# DIP_SWITCH.net
KiCad netlist of a schematic drawn in Altium Designer
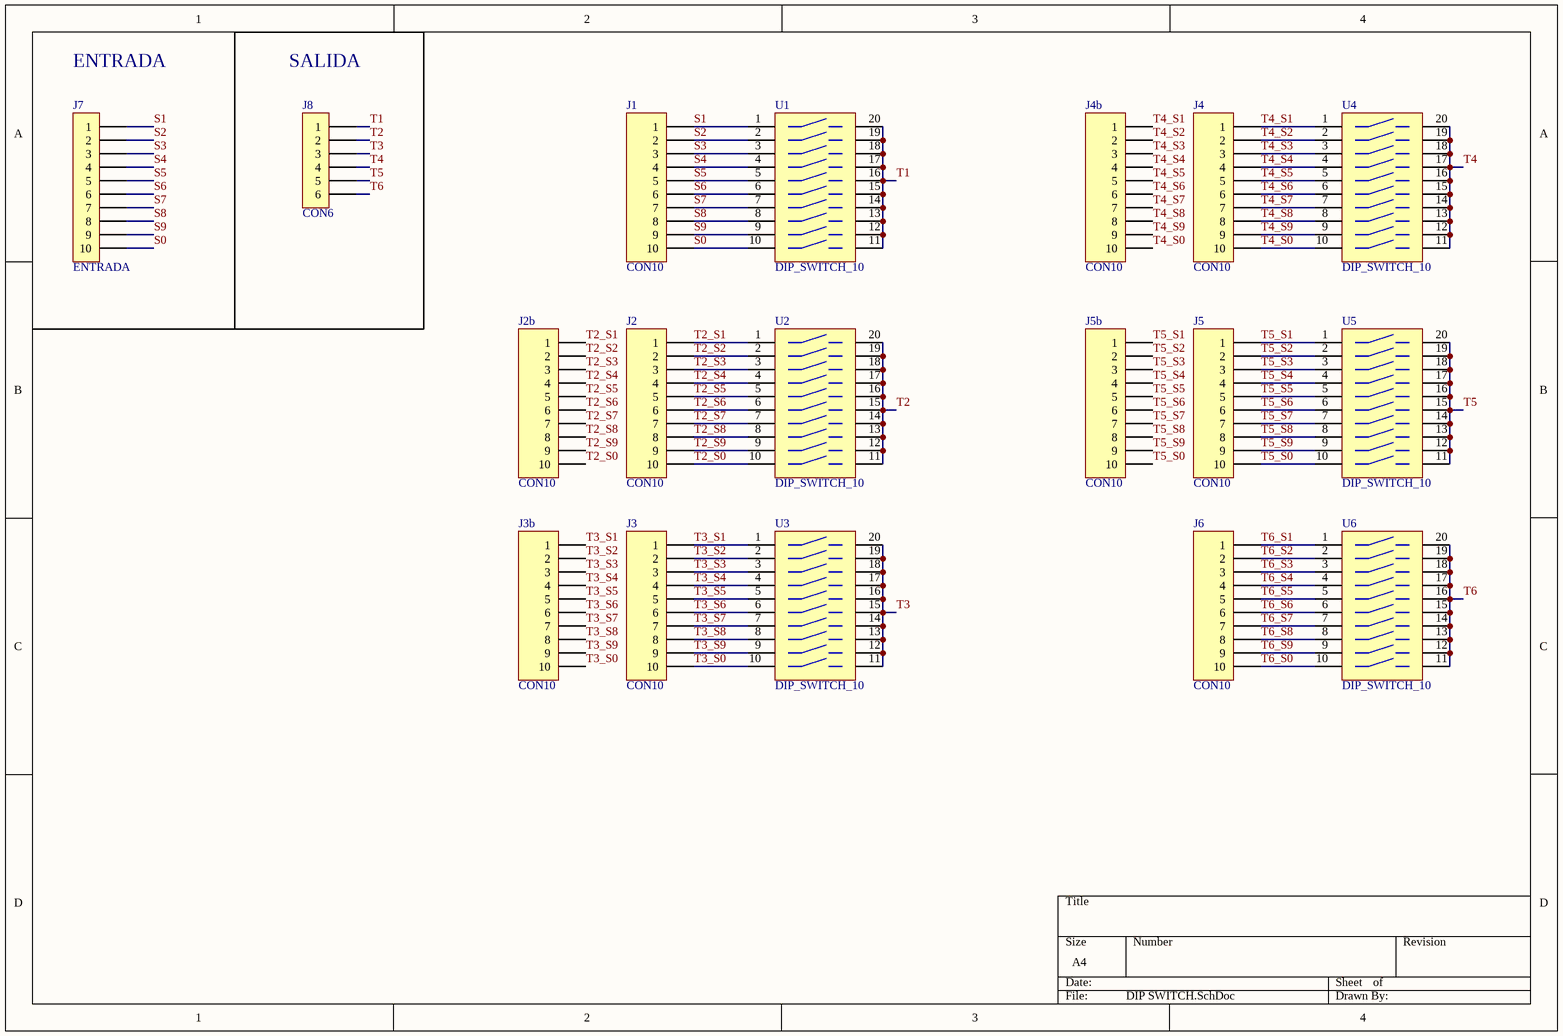
[diagram p0: DIP SWITCH.SchDoc]

(export (version "E")
  (design (tool "Eeschema 10.0.6"))
  (components
    (comp (ref "J1") (value "CON10") (footprint "SIP10") (libsource (lib "Libreria4") (part "CON10")))
    (comp (ref "J2") (value "CON10") (footprint "SIP10") (libsource (lib "Libreria4") (part "CON10")))
    (comp (ref "J2b") (value "CON10") (footprint "SIP10") (libsource (lib "Libreria4") (part "CON10")))
    (comp (ref "J3") (value "CON10") (footprint "SIP10") (libsource (lib "Libreria4") (part "CON10")))
    (comp (ref "J3b") (value "CON10") (footprint "SIP10") (libsource (lib "Libreria4") (part "CON10")))
    (comp (ref "J4") (value "CON10") (footprint "SIP10") (libsource (lib "Libreria4") (part "CON10")))
    (comp (ref "J4b") (value "CON10") (footprint "SIP10") (libsource (lib "Libreria4") (part "CON10")))
    (comp (ref "J5") (value "CON10") (footprint "SIP10") (libsource (lib "Libreria4") (part "CON10")))
    (comp (ref "J5b") (value "CON10") (footprint "SIP10") (libsource (lib "Libreria4") (part "CON10")))
    (comp (ref "J6") (value "CON10") (footprint "SIP10") (libsource (lib "Libreria4") (part "CON10")))
    (comp (ref "J7")
      (value "ENTRADA")
      (footprint "BORNERA10")
      (libsource (lib "Libreria4") (part "BORNERA10"))
    )
    (comp (ref "J8") (value "CON6") (footprint "SIP6") (libsource (lib "Libreria4") (part "CON6")))
    (comp (ref "U1")
      (value "DIP_SWITCH_10")
      (footprint "DIP20")
      (description "Dip_Switch 10 Posiciones")
      (libsource (lib "Libreria Buena Onda V5") (part "DIPSWITCH10"))
    )
    (comp (ref "U2")
      (value "DIP_SWITCH_10")
      (footprint "DIP20")
      (description "Dip_Switch 10 Posiciones")
      (libsource (lib "Libreria Buena Onda V5") (part "DIPSWITCH10"))
    )
    (comp (ref "U3")
      (value "DIP_SWITCH_10")
      (footprint "DIP20")
      (description "Dip_Switch 10 Posiciones")
      (libsource (lib "Libreria Buena Onda V5") (part "DIPSWITCH10"))
    )
    (comp (ref "U4")
      (value "DIP_SWITCH_10")
      (footprint "DIP20")
      (description "Dip_Switch 10 Posiciones")
      (libsource (lib "Libreria Buena Onda V5") (part "DIPSWITCH10"))
    )
    (comp (ref "U5")
      (value "DIP_SWITCH_10")
      (footprint "DIP20")
      (description "Dip_Switch 10 Posiciones")
      (libsource (lib "Libreria Buena Onda V5") (part "DIPSWITCH10"))
    )
    (comp (ref "U6")
      (value "DIP_SWITCH_10")
      (footprint "DIP20")
      (description "Dip_Switch 10 Posiciones")
      (libsource (lib "Libreria Buena Onda V5") (part "DIPSWITCH10"))
    )
  )
  (nets
    (net (code "1") (name "/S0") (class "Default")
      (node (ref "J1") (pin "10") (pinfunction "10_10") (pintype "passive"))
      (node (ref "J7") (pin "10") (pinfunction "10_10") (pintype "passive"))
      (node (ref "U1") (pin "10") (pinfunction "10_10") (pintype "passive"))
    )
    (net (code "2") (name "/S1") (class "Default")
      (node (ref "J1") (pin "1") (pinfunction "1_1") (pintype "passive"))
      (node (ref "J7") (pin "1") (pinfunction "1_1") (pintype "passive"))
      (node (ref "U1") (pin "1") (pinfunction "1_1") (pintype "passive"))
    )
    (net (code "3") (name "/S2") (class "Default")
      (node (ref "J1") (pin "2") (pinfunction "2_2") (pintype "passive"))
      (node (ref "J7") (pin "2") (pinfunction "2_2") (pintype "passive"))
      (node (ref "U1") (pin "2") (pinfunction "2_2") (pintype "passive"))
    )
    (net (code "4") (name "/S3") (class "Default")
      (node (ref "J1") (pin "3") (pinfunction "3_3") (pintype "passive"))
      (node (ref "J7") (pin "3") (pinfunction "3_3") (pintype "passive"))
      (node (ref "U1") (pin "3") (pinfunction "3_3") (pintype "passive"))
    )
    (net (code "5") (name "/S4") (class "Default")
      (node (ref "J1") (pin "4") (pinfunction "4_4") (pintype "passive"))
      (node (ref "J7") (pin "4") (pinfunction "4_4") (pintype "passive"))
      (node (ref "U1") (pin "4") (pinfunction "4_4") (pintype "passive"))
    )
    (net (code "6") (name "/S5") (class "Default")
      (node (ref "J1") (pin "5") (pinfunction "5_5") (pintype "passive"))
      (node (ref "J7") (pin "5") (pinfunction "5_5") (pintype "passive"))
      (node (ref "U1") (pin "5") (pinfunction "5_5") (pintype "passive"))
    )
    (net (code "7") (name "/S6") (class "Default")
      (node (ref "J1") (pin "6") (pinfunction "6_6") (pintype "passive"))
      (node (ref "J7") (pin "6") (pinfunction "6_6") (pintype "passive"))
      (node (ref "U1") (pin "6") (pinfunction "6_6") (pintype "passive"))
    )
    (net (code "8") (name "/S7") (class "Default")
      (node (ref "J1") (pin "7") (pinfunction "7_7") (pintype "passive"))
      (node (ref "J7") (pin "7") (pinfunction "7_7") (pintype "passive"))
      (node (ref "U1") (pin "7") (pinfunction "7_7") (pintype "passive"))
    )
    (net (code "9") (name "/S8") (class "Default")
      (node (ref "J1") (pin "8") (pinfunction "8_8") (pintype "passive"))
      (node (ref "J7") (pin "8") (pinfunction "8_8") (pintype "passive"))
      (node (ref "U1") (pin "8") (pinfunction "8_8") (pintype "passive"))
    )
    (net (code "10") (name "/S9") (class "Default")
      (node (ref "J1") (pin "9") (pinfunction "9_9") (pintype "passive"))
      (node (ref "J7") (pin "9") (pinfunction "9_9") (pintype "passive"))
      (node (ref "U1") (pin "9") (pinfunction "9_9") (pintype "passive"))
    )
    (net (code "11") (name "/T1") (class "Default")
      (node (ref "J8") (pin "1") (pinfunction "1_1") (pintype "passive"))
      (node (ref "U1") (pin "11") (pinfunction "11_11") (pintype "passive"))
      (node (ref "U1") (pin "12") (pinfunction "12_12") (pintype "passive"))
      (node (ref "U1") (pin "13") (pinfunction "13_13") (pintype "passive"))
      (node (ref "U1") (pin "14") (pinfunction "14_14") (pintype "passive"))
      (node (ref "U1") (pin "15") (pinfunction "15_15") (pintype "passive"))
      (node (ref "U1") (pin "16") (pinfunction "16_16") (pintype "passive"))
      (node (ref "U1") (pin "17") (pinfunction "17_17") (pintype "passive"))
      (node (ref "U1") (pin "18") (pinfunction "18_18") (pintype "passive"))
      (node (ref "U1") (pin "19") (pinfunction "19_19") (pintype "passive"))
      (node (ref "U1") (pin "20") (pinfunction "20_20") (pintype "passive"))
    )
    (net (code "12") (name "/T2") (class "Default")
      (node (ref "J8") (pin "2") (pinfunction "2_2") (pintype "passive"))
      (node (ref "U2") (pin "11") (pinfunction "11_11") (pintype "passive"))
      (node (ref "U2") (pin "12") (pinfunction "12_12") (pintype "passive"))
      (node (ref "U2") (pin "13") (pinfunction "13_13") (pintype "passive"))
      (node (ref "U2") (pin "14") (pinfunction "14_14") (pintype "passive"))
      (node (ref "U2") (pin "15") (pinfunction "15_15") (pintype "passive"))
      (node (ref "U2") (pin "16") (pinfunction "16_16") (pintype "passive"))
      (node (ref "U2") (pin "17") (pinfunction "17_17") (pintype "passive"))
      (node (ref "U2") (pin "18") (pinfunction "18_18") (pintype "passive"))
      (node (ref "U2") (pin "19") (pinfunction "19_19") (pintype "passive"))
      (node (ref "U2") (pin "20") (pinfunction "20_20") (pintype "passive"))
    )
    (net (code "13") (name "/T2_S0") (class "Default")
      (node (ref "J2") (pin "10") (pinfunction "10_10") (pintype "passive"))
      (node (ref "J2b") (pin "10") (pinfunction "10_10") (pintype "passive"))
      (node (ref "U2") (pin "10") (pinfunction "10_10") (pintype "passive"))
    )
    (net (code "14") (name "/T2_S1") (class "Default")
      (node (ref "J2") (pin "1") (pinfunction "1_1") (pintype "passive"))
      (node (ref "J2b") (pin "1") (pinfunction "1_1") (pintype "passive"))
      (node (ref "U2") (pin "1") (pinfunction "1_1") (pintype "passive"))
    )
    (net (code "15") (name "/T2_S2") (class "Default")
      (node (ref "J2") (pin "2") (pinfunction "2_2") (pintype "passive"))
      (node (ref "J2b") (pin "2") (pinfunction "2_2") (pintype "passive"))
      (node (ref "U2") (pin "2") (pinfunction "2_2") (pintype "passive"))
    )
    (net (code "16") (name "/T2_S3") (class "Default")
      (node (ref "J2") (pin "3") (pinfunction "3_3") (pintype "passive"))
      (node (ref "J2b") (pin "3") (pinfunction "3_3") (pintype "passive"))
      (node (ref "U2") (pin "3") (pinfunction "3_3") (pintype "passive"))
    )
    (net (code "17") (name "/T2_S4") (class "Default")
      (node (ref "J2") (pin "4") (pinfunction "4_4") (pintype "passive"))
      (node (ref "J2b") (pin "4") (pinfunction "4_4") (pintype "passive"))
      (node (ref "U2") (pin "4") (pinfunction "4_4") (pintype "passive"))
    )
    (net (code "18") (name "/T2_S5") (class "Default")
      (node (ref "J2") (pin "5") (pinfunction "5_5") (pintype "passive"))
      (node (ref "J2b") (pin "5") (pinfunction "5_5") (pintype "passive"))
      (node (ref "U2") (pin "5") (pinfunction "5_5") (pintype "passive"))
    )
    (net (code "19") (name "/T2_S6") (class "Default")
      (node (ref "J2") (pin "6") (pinfunction "6_6") (pintype "passive"))
      (node (ref "J2b") (pin "6") (pinfunction "6_6") (pintype "passive"))
      (node (ref "U2") (pin "6") (pinfunction "6_6") (pintype "passive"))
    )
    (net (code "20") (name "/T2_S7") (class "Default")
      (node (ref "J2") (pin "7") (pinfunction "7_7") (pintype "passive"))
      (node (ref "J2b") (pin "7") (pinfunction "7_7") (pintype "passive"))
      (node (ref "U2") (pin "7") (pinfunction "7_7") (pintype "passive"))
    )
    (net (code "21") (name "/T2_S8") (class "Default")
      (node (ref "J2") (pin "8") (pinfunction "8_8") (pintype "passive"))
      (node (ref "J2b") (pin "8") (pinfunction "8_8") (pintype "passive"))
      (node (ref "U2") (pin "8") (pinfunction "8_8") (pintype "passive"))
    )
    (net (code "22") (name "/T2_S9") (class "Default")
      (node (ref "J2") (pin "9") (pinfunction "9_9") (pintype "passive"))
      (node (ref "J2b") (pin "9") (pinfunction "9_9") (pintype "passive"))
      (node (ref "U2") (pin "9") (pinfunction "9_9") (pintype "passive"))
    )
    (net (code "23") (name "/T3") (class "Default")
      (node (ref "J8") (pin "3") (pinfunction "3_3") (pintype "passive"))
      (node (ref "U3") (pin "11") (pinfunction "11_11") (pintype "passive"))
      (node (ref "U3") (pin "12") (pinfunction "12_12") (pintype "passive"))
      (node (ref "U3") (pin "13") (pinfunction "13_13") (pintype "passive"))
      (node (ref "U3") (pin "14") (pinfunction "14_14") (pintype "passive"))
      (node (ref "U3") (pin "15") (pinfunction "15_15") (pintype "passive"))
      (node (ref "U3") (pin "16") (pinfunction "16_16") (pintype "passive"))
      (node (ref "U3") (pin "17") (pinfunction "17_17") (pintype "passive"))
      (node (ref "U3") (pin "18") (pinfunction "18_18") (pintype "passive"))
      (node (ref "U3") (pin "19") (pinfunction "19_19") (pintype "passive"))
      (node (ref "U3") (pin "20") (pinfunction "20_20") (pintype "passive"))
    )
    (net (code "24") (name "/T3_S0") (class "Default")
      (node (ref "J3") (pin "10") (pinfunction "10_10") (pintype "passive"))
      (node (ref "J3b") (pin "10") (pinfunction "10_10") (pintype "passive"))
      (node (ref "U3") (pin "10") (pinfunction "10_10") (pintype "passive"))
    )
    (net (code "25") (name "/T3_S1") (class "Default")
      (node (ref "J3") (pin "1") (pinfunction "1_1") (pintype "passive"))
      (node (ref "J3b") (pin "1") (pinfunction "1_1") (pintype "passive"))
      (node (ref "U3") (pin "1") (pinfunction "1_1") (pintype "passive"))
    )
    (net (code "26") (name "/T3_S2") (class "Default")
      (node (ref "J3") (pin "2") (pinfunction "2_2") (pintype "passive"))
      (node (ref "J3b") (pin "2") (pinfunction "2_2") (pintype "passive"))
      (node (ref "U3") (pin "2") (pinfunction "2_2") (pintype "passive"))
    )
    (net (code "27") (name "/T3_S3") (class "Default")
      (node (ref "J3") (pin "3") (pinfunction "3_3") (pintype "passive"))
      (node (ref "J3b") (pin "3") (pinfunction "3_3") (pintype "passive"))
      (node (ref "U3") (pin "3") (pinfunction "3_3") (pintype "passive"))
    )
    (net (code "28") (name "/T3_S4") (class "Default")
      (node (ref "J3") (pin "4") (pinfunction "4_4") (pintype "passive"))
      (node (ref "J3b") (pin "4") (pinfunction "4_4") (pintype "passive"))
      (node (ref "U3") (pin "4") (pinfunction "4_4") (pintype "passive"))
    )
    (net (code "29") (name "/T3_S5") (class "Default")
      (node (ref "J3") (pin "5") (pinfunction "5_5") (pintype "passive"))
      (node (ref "J3b") (pin "5") (pinfunction "5_5") (pintype "passive"))
      (node (ref "U3") (pin "5") (pinfunction "5_5") (pintype "passive"))
    )
    (net (code "30") (name "/T3_S6") (class "Default")
      (node (ref "J3") (pin "6") (pinfunction "6_6") (pintype "passive"))
      (node (ref "J3b") (pin "6") (pinfunction "6_6") (pintype "passive"))
      (node (ref "U3") (pin "6") (pinfunction "6_6") (pintype "passive"))
    )
    (net (code "31") (name "/T3_S7") (class "Default")
      (node (ref "J3") (pin "7") (pinfunction "7_7") (pintype "passive"))
      (node (ref "J3b") (pin "7") (pinfunction "7_7") (pintype "passive"))
      (node (ref "U3") (pin "7") (pinfunction "7_7") (pintype "passive"))
    )
    (net (code "32") (name "/T3_S8") (class "Default")
      (node (ref "J3") (pin "8") (pinfunction "8_8") (pintype "passive"))
      (node (ref "J3b") (pin "8") (pinfunction "8_8") (pintype "passive"))
      (node (ref "U3") (pin "8") (pinfunction "8_8") (pintype "passive"))
    )
    (net (code "33") (name "/T3_S9") (class "Default")
      (node (ref "J3") (pin "9") (pinfunction "9_9") (pintype "passive"))
      (node (ref "J3b") (pin "9") (pinfunction "9_9") (pintype "passive"))
      (node (ref "U3") (pin "9") (pinfunction "9_9") (pintype "passive"))
    )
    (net (code "34") (name "/T4") (class "Default")
      (node (ref "J8") (pin "4") (pinfunction "4_4") (pintype "passive"))
      (node (ref "U4") (pin "11") (pinfunction "11_11") (pintype "passive"))
      (node (ref "U4") (pin "12") (pinfunction "12_12") (pintype "passive"))
      (node (ref "U4") (pin "13") (pinfunction "13_13") (pintype "passive"))
      (node (ref "U4") (pin "14") (pinfunction "14_14") (pintype "passive"))
      (node (ref "U4") (pin "15") (pinfunction "15_15") (pintype "passive"))
      (node (ref "U4") (pin "16") (pinfunction "16_16") (pintype "passive"))
      (node (ref "U4") (pin "17") (pinfunction "17_17") (pintype "passive"))
      (node (ref "U4") (pin "18") (pinfunction "18_18") (pintype "passive"))
      (node (ref "U4") (pin "19") (pinfunction "19_19") (pintype "passive"))
      (node (ref "U4") (pin "20") (pinfunction "20_20") (pintype "passive"))
    )
    (net (code "35") (name "/T4_S0") (class "Default")
      (node (ref "J4") (pin "10") (pinfunction "10_10") (pintype "passive"))
      (node (ref "J4b") (pin "10") (pinfunction "10_10") (pintype "passive"))
      (node (ref "U4") (pin "10") (pinfunction "10_10") (pintype "passive"))
    )
    (net (code "36") (name "/T4_S1") (class "Default")
      (node (ref "J4") (pin "1") (pinfunction "1_1") (pintype "passive"))
      (node (ref "J4b") (pin "1") (pinfunction "1_1") (pintype "passive"))
      (node (ref "U4") (pin "1") (pinfunction "1_1") (pintype "passive"))
    )
    (net (code "37") (name "/T4_S2") (class "Default")
      (node (ref "J4") (pin "2") (pinfunction "2_2") (pintype "passive"))
      (node (ref "J4b") (pin "2") (pinfunction "2_2") (pintype "passive"))
      (node (ref "U4") (pin "2") (pinfunction "2_2") (pintype "passive"))
    )
    (net (code "38") (name "/T4_S3") (class "Default")
      (node (ref "J4") (pin "3") (pinfunction "3_3") (pintype "passive"))
      (node (ref "J4b") (pin "3") (pinfunction "3_3") (pintype "passive"))
      (node (ref "U4") (pin "3") (pinfunction "3_3") (pintype "passive"))
    )
    (net (code "39") (name "/T4_S4") (class "Default")
      (node (ref "J4") (pin "4") (pinfunction "4_4") (pintype "passive"))
      (node (ref "J4b") (pin "4") (pinfunction "4_4") (pintype "passive"))
      (node (ref "U4") (pin "4") (pinfunction "4_4") (pintype "passive"))
    )
    (net (code "40") (name "/T4_S5") (class "Default")
      (node (ref "J4") (pin "5") (pinfunction "5_5") (pintype "passive"))
      (node (ref "J4b") (pin "5") (pinfunction "5_5") (pintype "passive"))
      (node (ref "U4") (pin "5") (pinfunction "5_5") (pintype "passive"))
    )
    (net (code "41") (name "/T4_S6") (class "Default")
      (node (ref "J4") (pin "6") (pinfunction "6_6") (pintype "passive"))
      (node (ref "J4b") (pin "6") (pinfunction "6_6") (pintype "passive"))
      (node (ref "U4") (pin "6") (pinfunction "6_6") (pintype "passive"))
    )
    (net (code "42") (name "/T4_S7") (class "Default")
      (node (ref "J4") (pin "7") (pinfunction "7_7") (pintype "passive"))
      (node (ref "J4b") (pin "7") (pinfunction "7_7") (pintype "passive"))
      (node (ref "U4") (pin "7") (pinfunction "7_7") (pintype "passive"))
    )
    (net (code "43") (name "/T4_S8") (class "Default")
      (node (ref "J4") (pin "8") (pinfunction "8_8") (pintype "passive"))
      (node (ref "J4b") (pin "8") (pinfunction "8_8") (pintype "passive"))
      (node (ref "U4") (pin "8") (pinfunction "8_8") (pintype "passive"))
    )
    (net (code "44") (name "/T4_S9") (class "Default")
      (node (ref "J4") (pin "9") (pinfunction "9_9") (pintype "passive"))
      (node (ref "J4b") (pin "9") (pinfunction "9_9") (pintype "passive"))
      (node (ref "U4") (pin "9") (pinfunction "9_9") (pintype "passive"))
    )
    (net (code "45") (name "/T5") (class "Default")
      (node (ref "J8") (pin "5") (pinfunction "5_5") (pintype "passive"))
      (node (ref "U5") (pin "11") (pinfunction "11_11") (pintype "passive"))
      (node (ref "U5") (pin "12") (pinfunction "12_12") (pintype "passive"))
      (node (ref "U5") (pin "13") (pinfunction "13_13") (pintype "passive"))
      (node (ref "U5") (pin "14") (pinfunction "14_14") (pintype "passive"))
      (node (ref "U5") (pin "15") (pinfunction "15_15") (pintype "passive"))
      (node (ref "U5") (pin "16") (pinfunction "16_16") (pintype "passive"))
      (node (ref "U5") (pin "17") (pinfunction "17_17") (pintype "passive"))
      (node (ref "U5") (pin "18") (pinfunction "18_18") (pintype "passive"))
      (node (ref "U5") (pin "19") (pinfunction "19_19") (pintype "passive"))
      (node (ref "U5") (pin "20") (pinfunction "20_20") (pintype "passive"))
    )
    (net (code "46") (name "/T5_S0") (class "Default")
      (node (ref "J5") (pin "10") (pinfunction "10_10") (pintype "passive"))
      (node (ref "J5b") (pin "10") (pinfunction "10_10") (pintype "passive"))
      (node (ref "U5") (pin "10") (pinfunction "10_10") (pintype "passive"))
    )
    (net (code "47") (name "/T5_S1") (class "Default")
      (node (ref "J5") (pin "1") (pinfunction "1_1") (pintype "passive"))
      (node (ref "J5b") (pin "1") (pinfunction "1_1") (pintype "passive"))
      (node (ref "U5") (pin "1") (pinfunction "1_1") (pintype "passive"))
    )
    (net (code "48") (name "/T5_S2") (class "Default")
      (node (ref "J5") (pin "2") (pinfunction "2_2") (pintype "passive"))
      (node (ref "J5b") (pin "2") (pinfunction "2_2") (pintype "passive"))
      (node (ref "U5") (pin "2") (pinfunction "2_2") (pintype "passive"))
    )
    (net (code "49") (name "/T5_S3") (class "Default")
      (node (ref "J5") (pin "3") (pinfunction "3_3") (pintype "passive"))
      (node (ref "J5b") (pin "3") (pinfunction "3_3") (pintype "passive"))
      (node (ref "U5") (pin "3") (pinfunction "3_3") (pintype "passive"))
    )
    (net (code "50") (name "/T5_S4") (class "Default")
      (node (ref "J5") (pin "4") (pinfunction "4_4") (pintype "passive"))
      (node (ref "J5b") (pin "4") (pinfunction "4_4") (pintype "passive"))
      (node (ref "U5") (pin "4") (pinfunction "4_4") (pintype "passive"))
    )
    (net (code "51") (name "/T5_S5") (class "Default")
      (node (ref "J5") (pin "5") (pinfunction "5_5") (pintype "passive"))
      (node (ref "J5b") (pin "5") (pinfunction "5_5") (pintype "passive"))
      (node (ref "U5") (pin "5") (pinfunction "5_5") (pintype "passive"))
    )
    (net (code "52") (name "/T5_S6") (class "Default")
      (node (ref "J5") (pin "6") (pinfunction "6_6") (pintype "passive"))
      (node (ref "J5b") (pin "6") (pinfunction "6_6") (pintype "passive"))
      (node (ref "U5") (pin "6") (pinfunction "6_6") (pintype "passive"))
    )
    (net (code "53") (name "/T5_S7") (class "Default")
      (node (ref "J5") (pin "7") (pinfunction "7_7") (pintype "passive"))
      (node (ref "J5b") (pin "7") (pinfunction "7_7") (pintype "passive"))
      (node (ref "U5") (pin "7") (pinfunction "7_7") (pintype "passive"))
    )
    (net (code "54") (name "/T5_S8") (class "Default")
      (node (ref "J5") (pin "8") (pinfunction "8_8") (pintype "passive"))
      (node (ref "J5b") (pin "8") (pinfunction "8_8") (pintype "passive"))
      (node (ref "U5") (pin "8") (pinfunction "8_8") (pintype "passive"))
    )
    (net (code "55") (name "/T5_S9") (class "Default")
      (node (ref "J5") (pin "9") (pinfunction "9_9") (pintype "passive"))
      (node (ref "J5b") (pin "9") (pinfunction "9_9") (pintype "passive"))
      (node (ref "U5") (pin "9") (pinfunction "9_9") (pintype "passive"))
    )
    (net (code "56") (name "/T6") (class "Default")
      (node (ref "J8") (pin "6") (pinfunction "6_6") (pintype "passive"))
      (node (ref "U6") (pin "11") (pinfunction "11_11") (pintype "passive"))
      (node (ref "U6") (pin "12") (pinfunction "12_12") (pintype "passive"))
      (node (ref "U6") (pin "13") (pinfunction "13_13") (pintype "passive"))
      (node (ref "U6") (pin "14") (pinfunction "14_14") (pintype "passive"))
      (node (ref "U6") (pin "15") (pinfunction "15_15") (pintype "passive"))
      (node (ref "U6") (pin "16") (pinfunction "16_16") (pintype "passive"))
      (node (ref "U6") (pin "17") (pinfunction "17_17") (pintype "passive"))
      (node (ref "U6") (pin "18") (pinfunction "18_18") (pintype "passive"))
      (node (ref "U6") (pin "19") (pinfunction "19_19") (pintype "passive"))
      (node (ref "U6") (pin "20") (pinfunction "20_20") (pintype "passive"))
    )
    (net (code "57") (name "/T6_S0") (class "Default")
      (node (ref "J6") (pin "10") (pinfunction "10_10") (pintype "passive"))
      (node (ref "U6") (pin "10") (pinfunction "10_10") (pintype "passive"))
    )
    (net (code "58") (name "/T6_S1") (class "Default")
      (node (ref "J6") (pin "1") (pinfunction "1_1") (pintype "passive"))
      (node (ref "U6") (pin "1") (pinfunction "1_1") (pintype "passive"))
    )
    (net (code "59") (name "/T6_S2") (class "Default")
      (node (ref "J6") (pin "2") (pinfunction "2_2") (pintype "passive"))
      (node (ref "U6") (pin "2") (pinfunction "2_2") (pintype "passive"))
    )
    (net (code "60") (name "/T6_S3") (class "Default")
      (node (ref "J6") (pin "3") (pinfunction "3_3") (pintype "passive"))
      (node (ref "U6") (pin "3") (pinfunction "3_3") (pintype "passive"))
    )
    (net (code "61") (name "/T6_S4") (class "Default")
      (node (ref "J6") (pin "4") (pinfunction "4_4") (pintype "passive"))
      (node (ref "U6") (pin "4") (pinfunction "4_4") (pintype "passive"))
    )
    (net (code "62") (name "/T6_S5") (class "Default")
      (node (ref "J6") (pin "5") (pinfunction "5_5") (pintype "passive"))
      (node (ref "U6") (pin "5") (pinfunction "5_5") (pintype "passive"))
    )
    (net (code "63") (name "/T6_S6") (class "Default")
      (node (ref "J6") (pin "6") (pinfunction "6_6") (pintype "passive"))
      (node (ref "U6") (pin "6") (pinfunction "6_6") (pintype "passive"))
    )
    (net (code "64") (name "/T6_S7") (class "Default")
      (node (ref "J6") (pin "7") (pinfunction "7_7") (pintype "passive"))
      (node (ref "U6") (pin "7") (pinfunction "7_7") (pintype "passive"))
    )
    (net (code "65") (name "/T6_S8") (class "Default")
      (node (ref "J6") (pin "8") (pinfunction "8_8") (pintype "passive"))
      (node (ref "U6") (pin "8") (pinfunction "8_8") (pintype "passive"))
    )
    (net (code "66") (name "/T6_S9") (class "Default")
      (node (ref "J6") (pin "9") (pinfunction "9_9") (pintype "passive"))
      (node (ref "U6") (pin "9") (pinfunction "9_9") (pintype "passive"))
    )
  )
)
